# DSO_Clock.net
KiCad netlist of a schematic drawn in Altium Designer
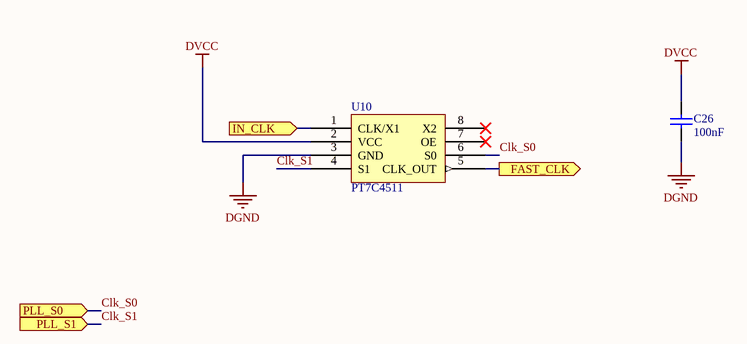
[diagram p0: DSO_Clock.SchDoc]

(export (version "E")
  (design (tool "Eeschema 10.0.6"))
  (components
    (comp (ref "C26")
      (value "100nF")
      (footprint "0805C")
      (description "Capacitor")
      (fields (field (name "REVIEWED BY") "RM - 2018/08/05"))
      (libsource (lib "DSO") (part "C"))
    )
    (comp (ref "U10")
      (value "PT7C4511")
      (footprint "SOIC-8")
      (description "PLL Clock Multiplier")
      (fields (field (name "REVIEWED BY") "RM - 2018/08/05"))
      (libsource (lib "DSO") (part "PT7C4511"))
    )
  )
  (nets
    (net (code "1") (name "/Clk_S0") (class "Default")
      (node (ref "U10") (pin "6") (pinfunction "S0_6") (pintype "passive"))
    )
    (net (code "2") (name "/Clk_S1") (class "Default")
      (node (ref "U10") (pin "4") (pinfunction "S1_4") (pintype "passive"))
    )
    (net (code "3") (name "/FAST_CLK") (class "Default")
      (node (ref "U10") (pin "5") (pinfunction "CLK_OUT_5") (pintype "output"))
    )
    (net (code "4") (name "/IN_CLK") (class "Default")
      (node (ref "U10") (pin "1") (pinfunction "CLK/X1_1") (pintype "passive"))
    )
    (net (code "5") (name "DGND") (class "Default")
      (node (ref "C26") (pin "2") (pinfunction "2_2") (pintype "passive"))
      (node (ref "U10") (pin "3") (pinfunction "GND_3") (pintype "passive"))
    )
    (net (code "6") (name "DVCC") (class "Default")
      (node (ref "C26") (pin "1") (pinfunction "1_1") (pintype "passive"))
      (node (ref "U10") (pin "2") (pinfunction "VCC_2") (pintype "passive"))
    )
    (net (code "7") (name "unconnected-(U10-OE-Pad7)") (class "Default")
      (node (ref "U10") (pin "7") (pinfunction "OE_7") (pintype "passive+no_connect"))
    )
    (net (code "8") (name "unconnected-(U10-X2-Pad8)") (class "Default")
      (node (ref "U10") (pin "8") (pinfunction "X2_8") (pintype "passive+no_connect"))
    )
  )
)
